# Audio_Bord.net
KiCad netlist of a schematic drawn in EAGLE
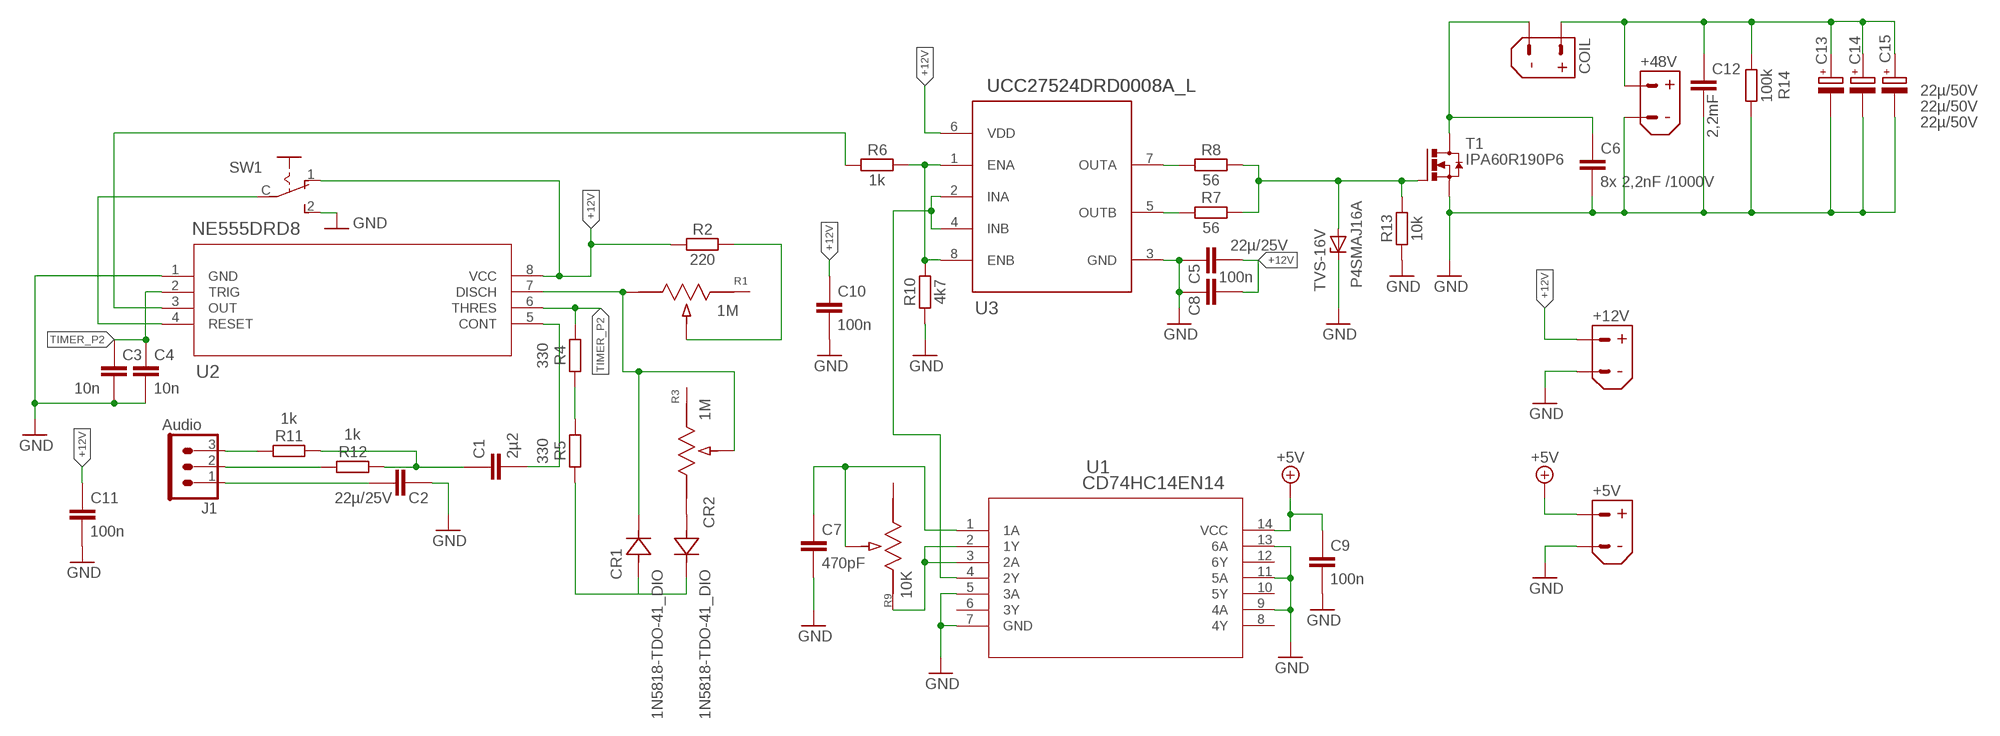
[diagram p0: schematic, sheet 1]

(export (version "E")
  (design (tool "Eeschema 10.0.6"))
  (components
    (comp (ref "+5V")
      (value "XT60UPB-M")
      (footprint "eagle-import:XT60UPB-M")
      (libsource (lib "eagle-import") (part "XT60?-MUPB"))
    )
    (comp (ref "+12V")
      (value "XT60UPB-M")
      (footprint "eagle-import:XT60UPB-M")
      (libsource (lib "eagle-import") (part "XT60?-MUPB"))
    )
    (comp (ref "+48V")
      (value "XT60UPB-M")
      (footprint "eagle-import:XT60UPB-M")
      (libsource (lib "eagle-import") (part "XT60?-MUPB"))
    )
    (comp (ref "C1")
      (value "2µ2")
      (footprint "eagle-import:C1206")
      (libsource (lib "eagle-import") (part "C-EU_-?C12062U2"))
    )
    (comp (ref "C2")
      (value "22µ/25V")
      (footprint "eagle-import:C1206")
      (libsource (lib "eagle-import") (part "C-EU_-?C120622U-25V"))
    )
    (comp (ref "C3")
      (value "10n")
      (footprint "eagle-import:C0603")
      (libsource (lib "eagle-import") (part "C-EU_-?C060310N"))
    )
    (comp (ref "C4")
      (value "10n")
      (footprint "eagle-import:C0603")
      (libsource (lib "eagle-import") (part "C-EU_-?C060310N"))
    )
    (comp (ref "C5")
      (value "22µ/25V")
      (footprint "eagle-import:C1206")
      (libsource (lib "eagle-import") (part "C-EU_-?C120622U-25V"))
    )
    (comp (ref "C6")
      (value "8x 2,2nF /1000V")
      (footprint "eagle-import:C1206")
      (libsource (lib "eagle-import") (part "C-EU_C1206"))
    )
    (comp (ref "C7")
      (value "470pF")
      (footprint "eagle-import:C1206")
      (libsource (lib "eagle-import") (part "C-EU_C1206"))
    )
    (comp (ref "C8")
      (value "100n")
      (footprint "eagle-import:C1206")
      (libsource (lib "eagle-import") (part "C-EU_-?C1206100N"))
    )
    (comp (ref "C9")
      (value "100n")
      (footprint "eagle-import:C1206")
      (libsource (lib "eagle-import") (part "C-EU_-?C1206100N"))
    )
    (comp (ref "C10")
      (value "100n")
      (footprint "eagle-import:C1206")
      (libsource (lib "eagle-import") (part "C-EU_-?C1206100N"))
    )
    (comp (ref "C11")
      (value "100n")
      (footprint "eagle-import:C1206")
      (libsource (lib "eagle-import") (part "C-EU_-?C1206100N"))
    )
    (comp (ref "C12")
      (value "2,2mF")
      (footprint "eagle-import:C1206")
      (libsource (lib "eagle-import") (part "C-EU_C1206"))
    )
    (comp (ref "C13")
      (value "22µ/50V")
      (footprint "eagle-import:E2-5")
      (libsource (lib "eagle-import") (part "CPOL-EU_-?E2-522U-50V"))
    )
    (comp (ref "C14")
      (value "22µ/50V")
      (footprint "eagle-import:E2-5")
      (libsource (lib "eagle-import") (part "CPOL-EU_-?E2-522U-50V"))
    )
    (comp (ref "C15")
      (value "22µ/50V")
      (footprint "eagle-import:E2-5")
      (libsource (lib "eagle-import") (part "CPOL-EU_-?E2-522U-50V"))
    )
    (comp (ref "COIL")
      (value "XT60UPB-M")
      (footprint "eagle-import:XT60UPB-M")
      (libsource (lib "eagle-import") (part "XT60?-MUPB"))
    )
    (comp (ref "CR1")
      (value "1N5818-TDO-41_DIO")
      (footprint "eagle-import:DO-41_DIO")
      (fields
        (field (name "MANUFACTURER_PART_NUMBER") "1N5818-T")
        (field (name "COPYRIGHT") "Copyright (C) 2026 Ultra Librarian. All rights reserved.")
      )
      (libsource (lib "eagle-import") (part "1N5818-TDO-41_DIO"))
    )
    (comp (ref "CR2")
      (value "1N5818-TDO-41_DIO")
      (footprint "eagle-import:DO-41_DIO")
      (fields
        (field (name "MANUFACTURER_PART_NUMBER") "1N5818-T")
        (field (name "COPYRIGHT") "Copyright (C) 2026 Ultra Librarian. All rights reserved.")
      )
      (libsource (lib "eagle-import") (part "1N5818-TDO-41_DIO"))
    )
    (comp (ref "J1")
      (value "Audio")
      (footprint "eagle-import:PSS-03G")
      (libsource (lib "eagle-import") (part "PSS-1X3G"))
    )
    (comp (ref "P4SMAJ16A")
      (value "TVS-16V")
      (footprint "eagle-import:DO214AC_SMA")
      (libsource (lib "eagle-import") (part "Z-DIODE--?DO214ACTSV-16V"))
    )
    (comp (ref "R1")
      (value "1M")
      (footprint "eagle-import:POT_3296X")
      (fields
        (field (name "MANUFACTURER_PART_NUMBER") "3296X-1-102LF")
        (field (name "COPYRIGHT") "Copyright (C) 2026 Ultra Librarian. All rights reserved.")
      )
      (libsource (lib "eagle-import") (part "3296X-1-102LFPOT_3296X"))
    )
    (comp (ref "R2")
      (value "220")
      (footprint "eagle-import:R1206")
      (libsource (lib "eagle-import") (part "R-EU_-?R1206220"))
    )
    (comp (ref "R3")
      (value "1M")
      (footprint "eagle-import:POT_3296X")
      (fields
        (field (name "MANUFACTURER_PART_NUMBER") "3296X-1-102LF")
        (field (name "COPYRIGHT") "Copyright (C) 2026 Ultra Librarian. All rights reserved.")
      )
      (libsource (lib "eagle-import") (part "3296X-1-102LFPOT_3296X"))
    )
    (comp (ref "R4")
      (value "330")
      (footprint "eagle-import:R0805")
      (libsource (lib "eagle-import") (part "R-EU_-?R0805330"))
    )
    (comp (ref "R5")
      (value "330")
      (footprint "eagle-import:R0805")
      (libsource (lib "eagle-import") (part "R-EU_-?R0805330"))
    )
    (comp (ref "R6")
      (value "1k")
      (footprint "eagle-import:R1206")
      (libsource (lib "eagle-import") (part "R-EU_-?R12061K"))
    )
    (comp (ref "R7")
      (value "56")
      (footprint "eagle-import:R1206")
      (libsource (lib "eagle-import") (part "R-EU_-?R120656"))
    )
    (comp (ref "R8")
      (value "56")
      (footprint "eagle-import:R1206")
      (libsource (lib "eagle-import") (part "R-EU_-?R120656"))
    )
    (comp (ref "R9")
      (value "10K")
      (footprint "eagle-import:POT_3296X")
      (fields
        (field (name "MANUFACTURER_PART_NUMBER") "3296X-1-102LF")
        (field (name "COPYRIGHT") "Copyright (C) 2026 Ultra Librarian. All rights reserved.")
      )
      (libsource (lib "eagle-import") (part "3296X-1-102LFPOT_3296X"))
    )
    (comp (ref "R10")
      (value "4k7")
      (footprint "eagle-import:R1206")
      (libsource (lib "eagle-import") (part "R-EU_-?R12064K7"))
    )
    (comp (ref "R11")
      (value "1k")
      (footprint "eagle-import:R1206")
      (libsource (lib "eagle-import") (part "R-EU_-?R12061K"))
    )
    (comp (ref "R12")
      (value "1k")
      (footprint "eagle-import:R1206")
      (libsource (lib "eagle-import") (part "R-EU_-?R12061K"))
    )
    (comp (ref "R13")
      (value "10k")
      (footprint "eagle-import:R1206")
      (libsource (lib "eagle-import") (part "R-EU_-?R120610K"))
    )
    (comp (ref "R14")
      (value "100k")
      (footprint "eagle-import:R1206")
      (libsource (lib "eagle-import") (part "R-EU_-?R1206100K"))
    )
    (comp (ref "SW1")
      (value "SW_SPDT_ESP10")
      (footprint "eagle-import:ESP10XX")
      (libsource (lib "eagle-import") (part "SW_SPDT_ESP10"))
    )
    (comp (ref "T1")
      (value "IPA60R190P6")
      (footprint "eagle-import:PG-TO263-3")
      (libsource (lib "eagle-import") (part "IPB020N10N5"))
    )
    (comp (ref "U1")
      (value "CD74HC14EN14")
      (footprint "eagle-import:N14")
      (fields
        (field (name "MANUFACTURER_PART_NUMBER") "CD74HC14E")
        (field (name "COPYRIGHT") "Copyright (C) 2026 Ultra Librarian. All rights reserved.")
      )
      (libsource (lib "eagle-import") (part "CD74HC14EN14"))
    )
    (comp (ref "U2")
      (value "NE555DRD8")
      (footprint "eagle-import:D8")
      (fields
        (field (name "MANUFACTURER_PART_NUMBER") "NE555DR")
        (field (name "COPYRIGHT") "Copyright (C) 2026 Ultra Librarian. All rights reserved.")
      )
      (libsource (lib "eagle-import") (part "NE555DRD8"))
    )
    (comp (ref "U3")
      (value "UCC27524DRD0008A_L")
      (footprint "eagle-import:D0008A_L")
      (fields
        (field (name "MANUFACTURER_PART_NUMBER") "UCC27524DR")
        (field (name "COPYRIGHT") "Copyright (C) 2026 Ultra Librarian. All rights reserved.")
      )
      (libsource (lib "eagle-import") (part "UCC27524DRD0008A_L"))
    )
  )
  (nets
    (net (code "1") (name "+5V") (class "Default")
      (node (ref "+5V") (pin "+") (pinfunction "+_+") (pintype "passive"))
      (node (ref "C9") (pin "1") (pinfunction "1_1") (pintype "passive"))
      (node (ref "U1") (pin "14") (pinfunction "VCC_14") (pintype "power_in"))
    )
    (net (code "2") (name "+12V") (class "Default")
      (node (ref "+12V") (pin "+") (pinfunction "+_+") (pintype "passive"))
      (node (ref "C10") (pin "1") (pinfunction "1_1") (pintype "passive"))
      (node (ref "C11") (pin "1") (pinfunction "1_1") (pintype "passive"))
      (node (ref "C5") (pin "2") (pinfunction "2_2") (pintype "passive"))
      (node (ref "C8") (pin "2") (pinfunction "2_2") (pintype "passive"))
      (node (ref "R2") (pin "1") (pinfunction "1_1") (pintype "passive"))
      (node (ref "SW1") (pin "1") (pinfunction "NC_1") (pintype "passive"))
      (node (ref "U2") (pin "8") (pinfunction "VCC_8") (pintype "power_in"))
      (node (ref "U3") (pin "6") (pinfunction "VDD_6") (pintype "power_in"))
    )
    (net (code "3") (name "GND") (class "Default")
      (node (ref "+12V") (pin "-") (pinfunction "-_-") (pintype "passive"))
      (node (ref "+48V") (pin "-") (pinfunction "-_-") (pintype "passive"))
      (node (ref "+5V") (pin "-") (pinfunction "-_-") (pintype "passive"))
      (node (ref "C10") (pin "2") (pinfunction "2_2") (pintype "passive"))
      (node (ref "C11") (pin "2") (pinfunction "2_2") (pintype "passive"))
      (node (ref "C12") (pin "2") (pinfunction "2_2") (pintype "passive"))
      (node (ref "C13") (pin "-") (pinfunction "-_-") (pintype "passive"))
      (node (ref "C14") (pin "-") (pinfunction "-_-") (pintype "passive"))
      (node (ref "C15") (pin "-") (pinfunction "-_-") (pintype "passive"))
      (node (ref "C2") (pin "2") (pinfunction "2_2") (pintype "passive"))
      (node (ref "C3") (pin "2") (pinfunction "2_2") (pintype "passive"))
      (node (ref "C4") (pin "2") (pinfunction "2_2") (pintype "passive"))
      (node (ref "C5") (pin "1") (pinfunction "1_1") (pintype "passive"))
      (node (ref "C6") (pin "2") (pinfunction "2_2") (pintype "passive"))
      (node (ref "C7") (pin "2") (pinfunction "2_2") (pintype "passive"))
      (node (ref "C8") (pin "1") (pinfunction "1_1") (pintype "passive"))
      (node (ref "C9") (pin "2") (pinfunction "2_2") (pintype "passive"))
      (node (ref "P4SMAJ16A") (pin "C") (pinfunction "C_C") (pintype "passive"))
      (node (ref "R10") (pin "1") (pinfunction "1_1") (pintype "passive"))
      (node (ref "R13") (pin "1") (pinfunction "1_1") (pintype "passive"))
      (node (ref "R14") (pin "1") (pinfunction "1_1") (pintype "passive"))
      (node (ref "SW1") (pin "2") (pinfunction "NO_2") (pintype "passive"))
      (node (ref "T1") (pin "3") (pinfunction "S_3") (pintype "passive"))
      (node (ref "U1") (pin "11") (pinfunction "5A_11") (pintype "input"))
      (node (ref "U1") (pin "13") (pinfunction "6A_13") (pintype "input"))
      (node (ref "U1") (pin "5") (pinfunction "3A_5") (pintype "input"))
      (node (ref "U1") (pin "7") (pinfunction "GND_7") (pintype "power_in"))
      (node (ref "U1") (pin "9") (pinfunction "4A_9") (pintype "input"))
      (node (ref "U2") (pin "1") (pinfunction "GND_1") (pintype "power_in"))
      (node (ref "U3") (pin "3") (pinfunction "GND_3") (pintype "power_in"))
    )
    (net (code "4") (name "Net-(+48V-Pad+)") (class "Default")
      (node (ref "+48V") (pin "+") (pinfunction "+_+") (pintype "passive"))
      (node (ref "C12") (pin "1") (pinfunction "1_1") (pintype "passive"))
      (node (ref "C13") (pin "+") (pinfunction "+_+") (pintype "passive"))
      (node (ref "C14") (pin "+") (pinfunction "+_+") (pintype "passive"))
      (node (ref "C15") (pin "+") (pinfunction "+_+") (pintype "passive"))
      (node (ref "COIL") (pin "+") (pinfunction "+_+") (pintype "passive"))
      (node (ref "R14") (pin "2") (pinfunction "2_2") (pintype "passive"))
    )
    (net (code "5") (name "Net-(C1-Pad1)") (class "Default")
      (node (ref "C1") (pin "1") (pinfunction "1_1") (pintype "passive"))
      (node (ref "R11") (pin "2") (pinfunction "2_2") (pintype "passive"))
      (node (ref "R12") (pin "2") (pinfunction "2_2") (pintype "passive"))
    )
    (net (code "6") (name "Net-(C2-Pad1)") (class "Default")
      (node (ref "C2") (pin "1") (pinfunction "1_1") (pintype "passive"))
      (node (ref "J1") (pin "1") (pinfunction "1_1") (pintype "passive"))
    )
    (net (code "7") (name "Net-(CR1-Pad2)") (class "Default")
      (node (ref "CR1") (pin "2") (pinfunction "2_2") (pintype "passive"))
      (node (ref "CR2") (pin "1") (pinfunction "1_1") (pintype "passive"))
      (node (ref "R5") (pin "1") (pinfunction "1_1") (pintype "passive"))
    )
    (net (code "8") (name "Net-(CR2-Pad2)") (class "Default")
      (node (ref "CR2") (pin "2") (pinfunction "2_2") (pintype "passive"))
      (node (ref "R3") (pin "3") (pinfunction "3_3") (pintype "passive"))
    )
    (net (code "9") (name "Net-(J1-Pad2)") (class "Default")
      (node (ref "J1") (pin "2") (pinfunction "2_2") (pintype "passive"))
      (node (ref "R12") (pin "1") (pinfunction "1_1") (pintype "passive"))
    )
    (net (code "10") (name "Net-(J1-Pad3)") (class "Default")
      (node (ref "J1") (pin "3") (pinfunction "3_3") (pintype "passive"))
      (node (ref "R11") (pin "1") (pinfunction "1_1") (pintype "passive"))
    )
    (net (code "11") (name "Net-(R1-Pad2)") (class "Default")
      (node (ref "R1") (pin "2") (pinfunction "2_2") (pintype "passive"))
      (node (ref "R2") (pin "2") (pinfunction "2_2") (pintype "passive"))
    )
    (net (code "12") (name "Net-(R4-Pad1)") (class "Default")
      (node (ref "R4") (pin "1") (pinfunction "1_1") (pintype "passive"))
      (node (ref "R5") (pin "2") (pinfunction "2_2") (pintype "passive"))
    )
    (net (code "13") (name "Net-(T1-D)") (class "Default")
      (node (ref "C6") (pin "1") (pinfunction "1_1") (pintype "passive"))
      (node (ref "COIL") (pin "-") (pinfunction "-_-") (pintype "passive"))
      (node (ref "T1") (pin "4") (pinfunction "D_4") (pintype "passive"))
    )
    (net (code "14") (name "Net-(T1-G)") (class "Default")
      (node (ref "P4SMAJ16A") (pin "A") (pinfunction "A_A") (pintype "passive"))
      (node (ref "R13") (pin "2") (pinfunction "2_2") (pintype "passive"))
      (node (ref "R7") (pin "2") (pinfunction "2_2") (pintype "passive"))
      (node (ref "R8") (pin "2") (pinfunction "2_2") (pintype "passive"))
      (node (ref "T1") (pin "1") (pinfunction "G_1") (pintype "passive"))
    )
    (net (code "15") (name "Net-(U1-1A)") (class "Default")
      (node (ref "C7") (pin "1") (pinfunction "1_1") (pintype "passive"))
      (node (ref "R9") (pin "2") (pinfunction "2_2") (pintype "passive"))
      (node (ref "U1") (pin "1") (pinfunction "1A_1") (pintype "input"))
    )
    (net (code "16") (name "Net-(U1-1Y)") (class "Default")
      (node (ref "R9") (pin "1") (pinfunction "1_1") (pintype "passive"))
      (node (ref "U1") (pin "2") (pinfunction "1Y_2") (pintype "output"))
      (node (ref "U1") (pin "3") (pinfunction "2A_3") (pintype "input"))
    )
    (net (code "17") (name "Net-(U1-2Y)") (class "Default")
      (node (ref "U1") (pin "4") (pinfunction "2Y_4") (pintype "output"))
      (node (ref "U3") (pin "2") (pinfunction "INA_2") (pintype "input"))
      (node (ref "U3") (pin "4") (pinfunction "INB_4") (pintype "input"))
    )
    (net (code "18") (name "Net-(U2-CONT)") (class "Default")
      (node (ref "C1") (pin "2") (pinfunction "2_2") (pintype "passive"))
      (node (ref "U2") (pin "5") (pinfunction "CONT_5") (pintype "passive"))
    )
    (net (code "19") (name "Net-(U2-DISCH)") (class "Default")
      (node (ref "CR1") (pin "1") (pinfunction "1_1") (pintype "passive"))
      (node (ref "R1") (pin "3") (pinfunction "3_3") (pintype "passive"))
      (node (ref "R3") (pin "2") (pinfunction "2_2") (pintype "passive"))
      (node (ref "U2") (pin "7") (pinfunction "DISCH_7") (pintype "passive"))
    )
    (net (code "20") (name "Net-(U2-OUT)") (class "Default")
      (node (ref "R6") (pin "1") (pinfunction "1_1") (pintype "passive"))
      (node (ref "U2") (pin "3") (pinfunction "OUT_3") (pintype "output"))
    )
    (net (code "21") (name "Net-(U2-RESET)") (class "Default")
      (node (ref "SW1") (pin "C") (pinfunction "C_C") (pintype "passive"))
      (node (ref "U2") (pin "4") (pinfunction "RESET_4") (pintype "input"))
    )
    (net (code "22") (name "Net-(U3-ENA)") (class "Default")
      (node (ref "R10") (pin "2") (pinfunction "2_2") (pintype "passive"))
      (node (ref "R6") (pin "2") (pinfunction "2_2") (pintype "passive"))
      (node (ref "U3") (pin "1") (pinfunction "ENA_1") (pintype "input"))
      (node (ref "U3") (pin "8") (pinfunction "ENB_8") (pintype "input"))
    )
    (net (code "23") (name "Net-(U3-OUTA)") (class "Default")
      (node (ref "R8") (pin "1") (pinfunction "1_1") (pintype "passive"))
      (node (ref "U3") (pin "7") (pinfunction "OUTA_7") (pintype "output"))
    )
    (net (code "24") (name "Net-(U3-OUTB)") (class "Default")
      (node (ref "R7") (pin "1") (pinfunction "1_1") (pintype "passive"))
      (node (ref "U3") (pin "5") (pinfunction "OUTB_5") (pintype "output"))
    )
    (net (code "25") (name "TIMER_P2") (class "Default")
      (node (ref "C3") (pin "1") (pinfunction "1_1") (pintype "passive"))
      (node (ref "C4") (pin "1") (pinfunction "1_1") (pintype "passive"))
      (node (ref "R4") (pin "2") (pinfunction "2_2") (pintype "passive"))
      (node (ref "U2") (pin "2") (pinfunction "TRIG_2") (pintype "input"))
      (node (ref "U2") (pin "6") (pinfunction "THRES_6") (pintype "input"))
    )
    (net (code "26") (name "unconnected-(R1-Pad1)") (class "Default")
      (node (ref "R1") (pin "1") (pinfunction "1_1") (pintype "passive"))
    )
    (net (code "27") (name "unconnected-(R3-Pad1)") (class "Default")
      (node (ref "R3") (pin "1") (pinfunction "1_1") (pintype "passive"))
    )
    (net (code "28") (name "unconnected-(R9-Pad3)") (class "Default")
      (node (ref "R9") (pin "3") (pinfunction "3_3") (pintype "passive"))
    )
    (net (code "29") (name "unconnected-(U1-3Y-Pad6)") (class "Default")
      (node (ref "U1") (pin "6") (pinfunction "3Y_6") (pintype "output"))
    )
    (net (code "30") (name "unconnected-(U1-4Y-Pad8)") (class "Default")
      (node (ref "U1") (pin "8") (pinfunction "4Y_8") (pintype "output"))
    )
    (net (code "31") (name "unconnected-(U1-5Y-Pad10)") (class "Default")
      (node (ref "U1") (pin "10") (pinfunction "5Y_10") (pintype "output"))
    )
    (net (code "32") (name "unconnected-(U1-6Y-Pad12)") (class "Default")
      (node (ref "U1") (pin "12") (pinfunction "6Y_12") (pintype "output"))
    )
  )
)
